# quadcopter-control-board.net
KiCad netlist of a schematic drawn in EAGLE
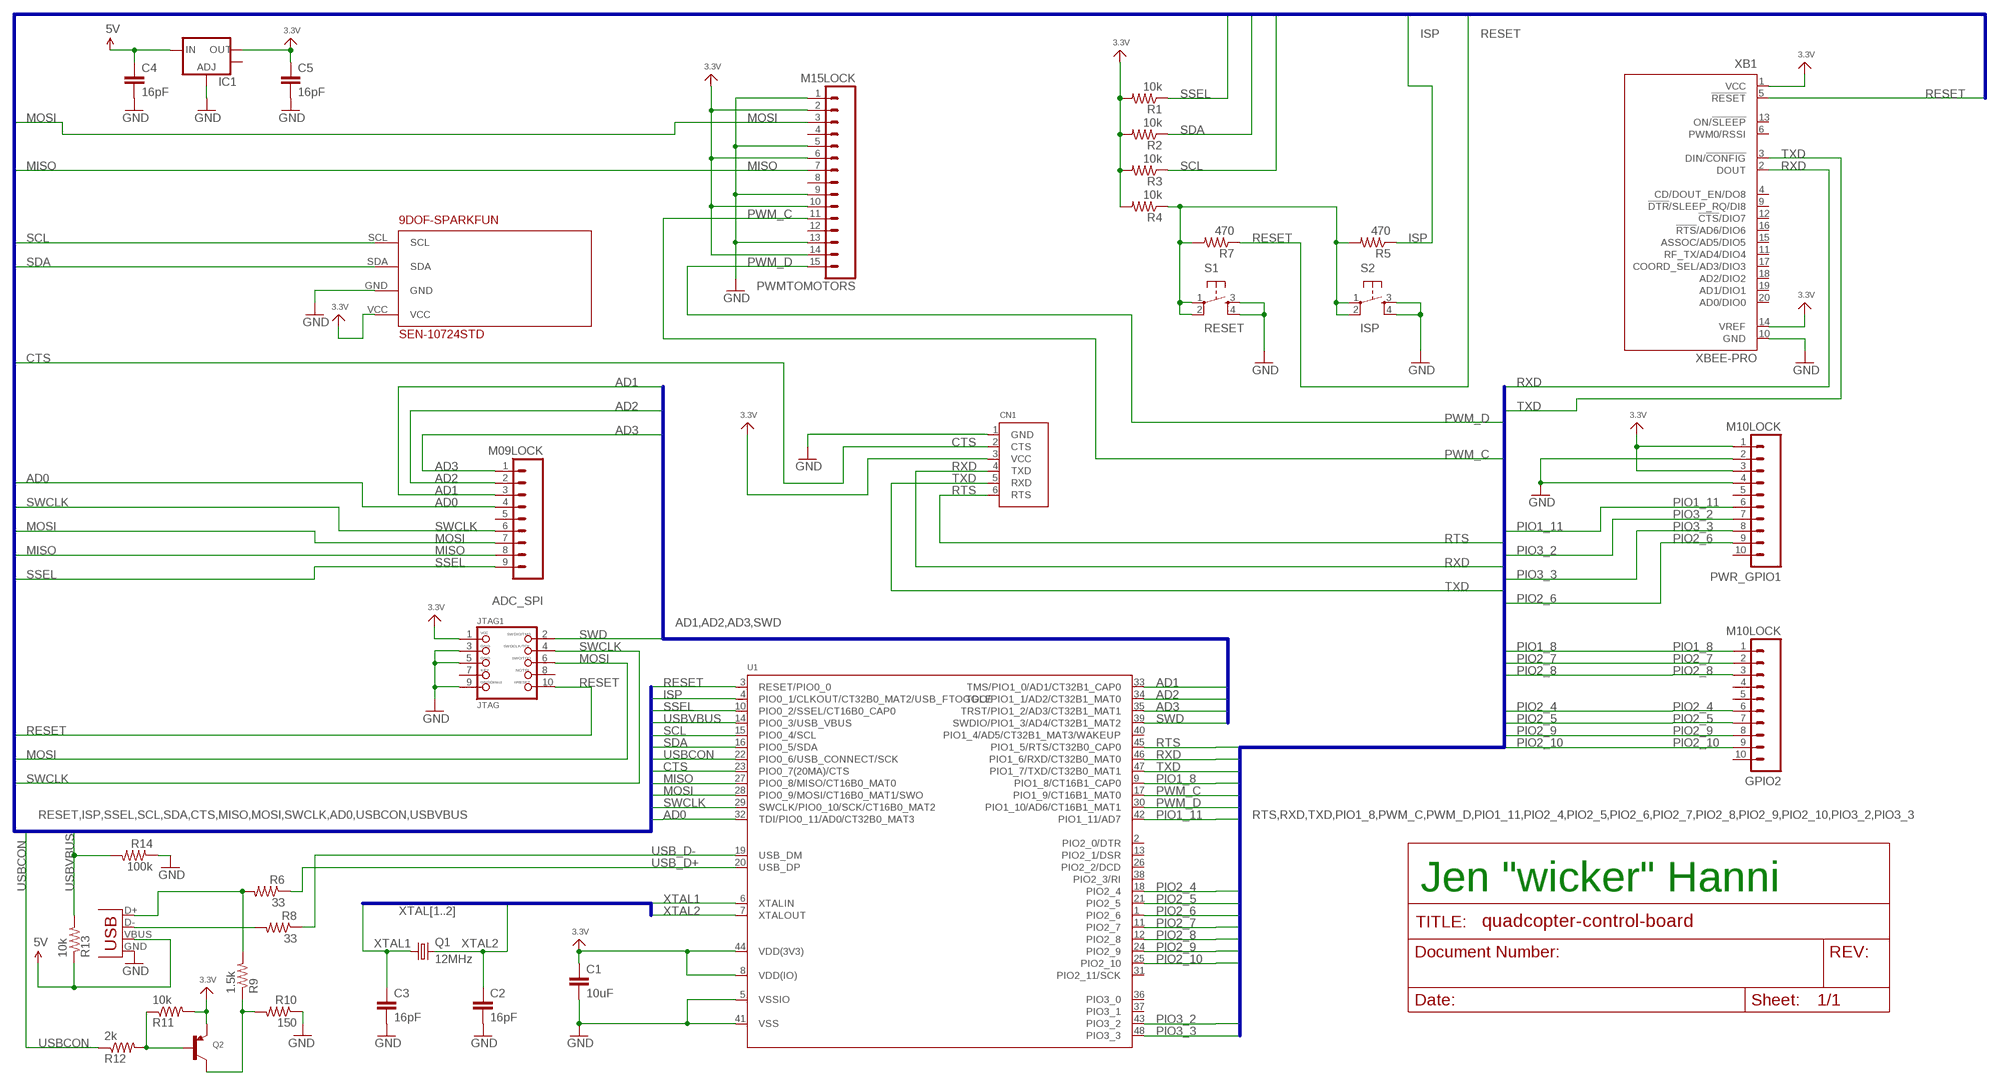
[diagram p0: schematic, sheet 1]

(export (version "E")
  (design (tool "Eeschema 10.0.6"))
  (components
    (comp (ref "9DOF-SPARKFUN")
      (value "SEN-10724STD")
      (footprint "eagle-import:SPARKFUN-9DOF")
      (libsource (lib "eagle-import") (part "SEN-10724STD"))
    )
    (comp (ref "ADC_SPI")
      (value "M09LOCK")
      (footprint "eagle-import:1X09_LOCK")
      (libsource (lib "eagle-import") (part "M09LOCK"))
    )
    (comp (ref "C1")
      (value "10uF")
      (footprint "eagle-import:0603-CAP")
      (libsource (lib "eagle-import") (part "CAP0603-CAP"))
    )
    (comp (ref "C2")
      (value "16pF")
      (footprint "eagle-import:0603-CAP")
      (libsource (lib "eagle-import") (part "CAP0603-CAP"))
    )
    (comp (ref "C3")
      (value "16pF")
      (footprint "eagle-import:0603-CAP")
      (libsource (lib "eagle-import") (part "CAP0603-CAP"))
    )
    (comp (ref "C4")
      (value "16pF")
      (footprint "eagle-import:0603-CAP")
      (libsource (lib "eagle-import") (part "CAP0603-CAP"))
    )
    (comp (ref "C5")
      (value "16pF")
      (footprint "eagle-import:0603-CAP")
      (libsource (lib "eagle-import") (part "CAP0603-CAP"))
    )
    (comp (ref "CN1")
      (value "FTDIUSBCABLE")
      (footprint "eagle-import:1X06_ROUND")
      (libsource (lib "eagle-import") (part "FTDIUSBCABLE"))
    )
    (comp (ref "GPIO2")
      (value "M10LOCK")
      (footprint "eagle-import:1X10_LOCK")
      (libsource (lib "eagle-import") (part "M10LOCK"))
    )
    (comp (ref "IC1")
      (value "V_REG_LM1117SOT223")
      (footprint "eagle-import:SOT223")
      (libsource (lib "eagle-import") (part "V_REG_LM1117SOT223"))
    )
    (comp (ref "JTAG1")
      (value "JTAG")
      (footprint "eagle-import:CORTEXM3_SWD10_MOLEX")
      (libsource (lib "eagle-import") (part "JTAG-CORTEXM3MOLEX"))
    )
    (comp (ref "PWMTOMOTORS")
      (value "M15LOCK")
      (footprint "eagle-import:1X15_LOCK")
      (libsource (lib "eagle-import") (part "M15LOCK"))
    )
    (comp (ref "PWR_GPIO1")
      (value "M10LOCK")
      (footprint "eagle-import:1X10_LOCK")
      (libsource (lib "eagle-import") (part "M10LOCK"))
    )
    (comp (ref "Q1")
      (value "12MHz")
      (footprint "eagle-import:CTS406")
      (libsource (lib "eagle-import") (part "CRYSTALCTS406"))
    )
    (comp (ref "Q2")
      (value "TRANSISTOR_PNPSOT23-REFLOW")
      (footprint "eagle-import:SOT23-R")
      (libsource (lib "eagle-import") (part "TRANSISTOR_PNPSOT23-REFLOW"))
    )
    (comp (ref "R1")
      (value "10k")
      (footprint "eagle-import:0603-RES")
      (libsource (lib "eagle-import") (part "RESISTOR0603-RES"))
    )
    (comp (ref "R2")
      (value "10k")
      (footprint "eagle-import:0603-RES")
      (libsource (lib "eagle-import") (part "RESISTOR0603-RES"))
    )
    (comp (ref "R3")
      (value "10k")
      (footprint "eagle-import:0603-RES")
      (libsource (lib "eagle-import") (part "RESISTOR0603-RES"))
    )
    (comp (ref "R4")
      (value "10k")
      (footprint "eagle-import:0603-RES")
      (libsource (lib "eagle-import") (part "RESISTOR0603-RES"))
    )
    (comp (ref "R5")
      (value "470")
      (footprint "eagle-import:0603-RES")
      (libsource (lib "eagle-import") (part "RESISTOR0603-RES"))
    )
    (comp (ref "R6")
      (value "33")
      (footprint "eagle-import:0603-RES")
      (libsource (lib "eagle-import") (part "RESISTOR0603-RES"))
    )
    (comp (ref "R7")
      (value "470")
      (footprint "eagle-import:0603-RES")
      (libsource (lib "eagle-import") (part "RESISTOR0603-RES"))
    )
    (comp (ref "R8")
      (value "33")
      (footprint "eagle-import:0603-RES")
      (libsource (lib "eagle-import") (part "RESISTOR0603-RES"))
    )
    (comp (ref "R9")
      (value "1.5k")
      (footprint "eagle-import:0603-RES")
      (libsource (lib "eagle-import") (part "RESISTOR0603-RES"))
    )
    (comp (ref "R10")
      (value "150")
      (footprint "eagle-import:0603-RES")
      (libsource (lib "eagle-import") (part "RESISTOR0603-RES"))
    )
    (comp (ref "R11")
      (value "10k")
      (footprint "eagle-import:0603-RES")
      (libsource (lib "eagle-import") (part "RESISTOR0603-RES"))
    )
    (comp (ref "R12")
      (value "2k")
      (footprint "eagle-import:0603-RES")
      (libsource (lib "eagle-import") (part "RESISTOR0603-RES"))
    )
    (comp (ref "R13")
      (value "10k")
      (footprint "eagle-import:0603-RES")
      (libsource (lib "eagle-import") (part "RESISTOR0603-RES"))
    )
    (comp (ref "R14")
      (value "100k")
      (footprint "eagle-import:0603-RES")
      (libsource (lib "eagle-import") (part "RESISTOR0603-RES"))
    )
    (comp (ref "S1")
      (value "RESET")
      (footprint "eagle-import:TACTILE_SWITCH_SMD")
      (libsource (lib "eagle-import") (part "TAC_SWITCHSMD"))
    )
    (comp (ref "S2")
      (value "ISP")
      (footprint "eagle-import:TACTILE_SWITCH_SMD")
      (libsource (lib "eagle-import") (part "TAC_SWITCHSMD"))
    )
    (comp (ref "U1")
      (value "LPC1343_QFP")
      (footprint "eagle-import:LQFP48")
      (fields (field (name "MANF") "NXP"))
      (libsource (lib "eagle-import") (part "LPC1343_QFP"))
    )
    (comp (ref "X1")
      (value "USB-SMD-NS")
      (footprint "eagle-import:USB-MINIB-NOSTOP")
      (libsource (lib "eagle-import") (part "USB-SMD-NS"))
    )
    (comp (ref "XB1")
      (value "XBEE-PRO")
      (footprint "eagle-import:XBEE-PRO")
      (libsource (lib "eagle-import") (part "XBEE-PRO"))
    )
  )
  (nets
    (net (code "1") (name "/AD0") (class "Default")
      (node (ref "ADC_SPI") (pin "4") (pinfunction "4_4") (pintype "passive"))
      (node (ref "U1") (pin "32") (pinfunction "TDI/PIO0_11/AD0/CT32B0_MAT3_32") (pintype "bidirectional"))
    )
    (net (code "2") (name "/AD1") (class "Default")
      (node (ref "ADC_SPI") (pin "3") (pinfunction "3_3") (pintype "passive"))
      (node (ref "U1") (pin "33") (pinfunction "TMS/PIO1_0/AD1/CT32B1_CAP0_33") (pintype "bidirectional"))
    )
    (net (code "3") (name "/AD2") (class "Default")
      (node (ref "ADC_SPI") (pin "2") (pinfunction "2_2") (pintype "passive"))
      (node (ref "U1") (pin "34") (pinfunction "TDO/PIO1_1/AD2/CT32B1_MAT0_34") (pintype "bidirectional"))
    )
    (net (code "4") (name "/AD3") (class "Default")
      (node (ref "ADC_SPI") (pin "1") (pinfunction "1_1") (pintype "passive"))
      (node (ref "U1") (pin "35") (pinfunction "TRST/PIO1_2/AD3/CT32B1_MAT1_35") (pintype "bidirectional"))
    )
    (net (code "5") (name "/CTS") (class "Default")
      (node (ref "CN1") (pin "2") (pinfunction "CTS_2") (pintype "bidirectional"))
      (node (ref "U1") (pin "23") (pinfunction "PIO0_7(20MA)/CTS_23") (pintype "bidirectional"))
    )
    (net (code "6") (name "/ISP") (class "Default")
      (node (ref "R5") (pin "1") (pinfunction "1_1") (pintype "passive"))
      (node (ref "U1") (pin "4") (pinfunction "PIO0_1/CLKOUT/CT32B0_MAT2/USB_FTOGGLE_4") (pintype "bidirectional"))
    )
    (net (code "7") (name "/MISO") (class "Default")
      (node (ref "ADC_SPI") (pin "8") (pinfunction "8_8") (pintype "passive"))
      (node (ref "PWMTOMOTORS") (pin "7") (pinfunction "7_7") (pintype "passive"))
      (node (ref "U1") (pin "27") (pinfunction "PIO0_8/MISO/CT16B0_MAT0_27") (pintype "bidirectional"))
    )
    (net (code "8") (name "/MOSI") (class "Default")
      (node (ref "ADC_SPI") (pin "7") (pinfunction "7_7") (pintype "passive"))
      (node (ref "JTAG1") (pin "6") (pinfunction "6_6") (pintype "passive"))
      (node (ref "PWMTOMOTORS") (pin "3") (pinfunction "3_3") (pintype "passive"))
      (node (ref "U1") (pin "28") (pinfunction "PIO0_9/MOSI/CT16B0_MAT1/SWO_28") (pintype "bidirectional"))
    )
    (net (code "9") (name "/PIO1_8") (class "Default")
      (node (ref "GPIO2") (pin "1") (pinfunction "1_1") (pintype "passive"))
      (node (ref "U1") (pin "9") (pinfunction "PIO1_8/CT16B1_CAP0_9") (pintype "bidirectional"))
    )
    (net (code "10") (name "/PIO1_11") (class "Default")
      (node (ref "PWR_GPIO1") (pin "6") (pinfunction "6_6") (pintype "passive"))
      (node (ref "U1") (pin "42") (pinfunction "PIO1_11/AD7_42") (pintype "bidirectional"))
    )
    (net (code "11") (name "/PIO2_4") (class "Default")
      (node (ref "GPIO2") (pin "6") (pinfunction "6_6") (pintype "passive"))
      (node (ref "U1") (pin "18") (pinfunction "PIO2_4_18") (pintype "bidirectional"))
    )
    (net (code "12") (name "/PIO2_5") (class "Default")
      (node (ref "GPIO2") (pin "7") (pinfunction "7_7") (pintype "passive"))
      (node (ref "U1") (pin "21") (pinfunction "PIO2_5_21") (pintype "bidirectional"))
    )
    (net (code "13") (name "/PIO2_6") (class "Default")
      (node (ref "PWR_GPIO1") (pin "9") (pinfunction "9_9") (pintype "passive"))
      (node (ref "U1") (pin "1") (pinfunction "PIO2_6_1") (pintype "bidirectional"))
    )
    (net (code "14") (name "/PIO2_7") (class "Default")
      (node (ref "GPIO2") (pin "2") (pinfunction "2_2") (pintype "passive"))
      (node (ref "U1") (pin "11") (pinfunction "PIO2_7_11") (pintype "bidirectional"))
    )
    (net (code "15") (name "/PIO2_8") (class "Default")
      (node (ref "GPIO2") (pin "3") (pinfunction "3_3") (pintype "passive"))
      (node (ref "U1") (pin "12") (pinfunction "PIO2_8_12") (pintype "bidirectional"))
    )
    (net (code "16") (name "/PIO2_9") (class "Default")
      (node (ref "GPIO2") (pin "8") (pinfunction "8_8") (pintype "passive"))
      (node (ref "U1") (pin "24") (pinfunction "PIO2_9_24") (pintype "bidirectional"))
    )
    (net (code "17") (name "/PIO2_10") (class "Default")
      (node (ref "GPIO2") (pin "9") (pinfunction "9_9") (pintype "passive"))
      (node (ref "U1") (pin "25") (pinfunction "PIO2_10_25") (pintype "bidirectional"))
    )
    (net (code "18") (name "/PIO3_2") (class "Default")
      (node (ref "PWR_GPIO1") (pin "7") (pinfunction "7_7") (pintype "passive"))
      (node (ref "U1") (pin "43") (pinfunction "PIO3_2_43") (pintype "bidirectional"))
    )
    (net (code "19") (name "/PIO3_3") (class "Default")
      (node (ref "PWR_GPIO1") (pin "8") (pinfunction "8_8") (pintype "passive"))
      (node (ref "U1") (pin "48") (pinfunction "PIO3_3_48") (pintype "bidirectional"))
    )
    (net (code "20") (name "/PWM_C") (class "Default")
      (node (ref "PWMTOMOTORS") (pin "11") (pinfunction "11_11") (pintype "passive"))
      (node (ref "U1") (pin "17") (pinfunction "PIO1_9/CT16B1_MAT0_17") (pintype "bidirectional"))
    )
    (net (code "21") (name "/PWM_D") (class "Default")
      (node (ref "PWMTOMOTORS") (pin "15") (pinfunction "15_15") (pintype "passive"))
      (node (ref "U1") (pin "30") (pinfunction "PIO1_10/AD6/CT16B1_MAT1_30") (pintype "bidirectional"))
    )
    (net (code "22") (name "/RESET") (class "Default")
      (node (ref "JTAG1") (pin "10") (pinfunction "10_10") (pintype "passive"))
      (node (ref "R7") (pin "1") (pinfunction "1_1") (pintype "passive"))
      (node (ref "U1") (pin "3") (pinfunction "RESET/PIO0_0_3") (pintype "bidirectional"))
      (node (ref "XB1") (pin "5") (pinfunction "~{RESET}_5") (pintype "input"))
    )
    (net (code "23") (name "/RTS") (class "Default")
      (node (ref "CN1") (pin "6") (pinfunction "RTS_6") (pintype "bidirectional"))
      (node (ref "U1") (pin "45") (pinfunction "PIO1_5/RTS/CT32B0_CAP0_45") (pintype "bidirectional"))
    )
    (net (code "24") (name "/RXD") (class "Default")
      (node (ref "CN1") (pin "4") (pinfunction "TXD_4") (pintype "bidirectional"))
      (node (ref "U1") (pin "46") (pinfunction "PIO1_6/RXD/CT32B0_MAT0_46") (pintype "bidirectional"))
      (node (ref "XB1") (pin "2") (pinfunction "DOUT_2") (pintype "output"))
    )
    (net (code "25") (name "/SCL") (class "Default")
      (node (ref "9DOF-SPARKFUN") (pin "SCL") (pinfunction "SCL_SCL") (pintype "bidirectional"))
      (node (ref "R3") (pin "1") (pinfunction "1_1") (pintype "passive"))
      (node (ref "U1") (pin "15") (pinfunction "PIO0_4/SCL_15") (pintype "bidirectional"))
    )
    (net (code "26") (name "/SDA") (class "Default")
      (node (ref "9DOF-SPARKFUN") (pin "SDA") (pinfunction "SDA_SDA") (pintype "bidirectional"))
      (node (ref "R2") (pin "1") (pinfunction "1_1") (pintype "passive"))
      (node (ref "U1") (pin "16") (pinfunction "PIO0_5/SDA_16") (pintype "bidirectional"))
    )
    (net (code "27") (name "/SSEL") (class "Default")
      (node (ref "ADC_SPI") (pin "9") (pinfunction "9_9") (pintype "passive"))
      (node (ref "R1") (pin "1") (pinfunction "1_1") (pintype "passive"))
      (node (ref "U1") (pin "10") (pinfunction "PIO0_2/SSEL/CT16B0_CAP0_10") (pintype "bidirectional"))
    )
    (net (code "28") (name "/SWCLK") (class "Default")
      (node (ref "ADC_SPI") (pin "6") (pinfunction "6_6") (pintype "passive"))
      (node (ref "JTAG1") (pin "4") (pinfunction "4_4") (pintype "passive"))
      (node (ref "U1") (pin "29") (pinfunction "SWCLK/PIO0_10/SCK/CT16B0_MAT2_29") (pintype "bidirectional"))
    )
    (net (code "29") (name "/SWD") (class "Default")
      (node (ref "JTAG1") (pin "2") (pinfunction "2_2") (pintype "passive"))
      (node (ref "U1") (pin "39") (pinfunction "SWDIO/PIO1_3/AD4/CT32B1_MAT2_39") (pintype "bidirectional"))
    )
    (net (code "30") (name "/TXD") (class "Default")
      (node (ref "CN1") (pin "5") (pinfunction "RXD_5") (pintype "bidirectional"))
      (node (ref "U1") (pin "47") (pinfunction "PIO1_7/TXD/CT32B0_MAT1_47") (pintype "bidirectional"))
      (node (ref "XB1") (pin "3") (pinfunction "DIN/~{CONFIG}_3") (pintype "input"))
    )
    (net (code "31") (name "/USBCON") (class "Default")
      (node (ref "R12") (pin "1") (pinfunction "1_1") (pintype "passive"))
      (node (ref "U1") (pin "22") (pinfunction "PIO0_6/USB_CONNECT/SCK_22") (pintype "bidirectional"))
    )
    (net (code "32") (name "/USBVBUS") (class "Default")
      (node (ref "R13") (pin "2") (pinfunction "2_2") (pintype "passive"))
      (node (ref "R14") (pin "2") (pinfunction "2_2") (pintype "passive"))
      (node (ref "U1") (pin "14") (pinfunction "PIO0_3/USB_VBUS_14") (pintype "bidirectional"))
    )
    (net (code "33") (name "/USB_D+") (class "Default")
      (node (ref "R6") (pin "1") (pinfunction "1_1") (pintype "passive"))
      (node (ref "U1") (pin "20") (pinfunction "USB_DP_20") (pintype "bidirectional"))
    )
    (net (code "34") (name "/USB_D-") (class "Default")
      (node (ref "R8") (pin "1") (pinfunction "1_1") (pintype "passive"))
      (node (ref "U1") (pin "19") (pinfunction "USB_DM_19") (pintype "bidirectional"))
    )
    (net (code "35") (name "/XTAL1") (class "Default")
      (node (ref "C3") (pin "1") (pinfunction "1_1") (pintype "passive"))
      (node (ref "Q1") (pin "1") (pinfunction "1_1") (pintype "passive"))
      (node (ref "U1") (pin "6") (pinfunction "XTALIN_6") (pintype "input"))
    )
    (net (code "36") (name "/XTAL2") (class "Default")
      (node (ref "C2") (pin "1") (pinfunction "1_1") (pintype "passive"))
      (node (ref "Q1") (pin "3") (pinfunction "2_3") (pintype "passive"))
      (node (ref "U1") (pin "7") (pinfunction "XTALOUT_7") (pintype "output"))
    )
    (net (code "41") (name "3.3V") (class "Default")
      (node (ref "9DOF-SPARKFUN") (pin "VCC") (pinfunction "VCC_VCC") (pintype "power_in"))
      (node (ref "C1") (pin "1") (pinfunction "1_1") (pintype "passive"))
      (node (ref "C5") (pin "1") (pinfunction "1_1") (pintype "passive"))
      (node (ref "CN1") (pin "3") (pinfunction "VCC_3") (pintype "bidirectional"))
      (node (ref "IC1") (pin "2") (pinfunction "OUT_2") (pintype "output"))
      (node (ref "JTAG1") (pin "1") (pinfunction "1_1") (pintype "passive"))
      (node (ref "PWMTOMOTORS") (pin "10") (pinfunction "10_10") (pintype "passive"))
      (node (ref "PWMTOMOTORS") (pin "14") (pinfunction "14_14") (pintype "passive"))
      (node (ref "PWMTOMOTORS") (pin "2") (pinfunction "2_2") (pintype "passive"))
      (node (ref "PWMTOMOTORS") (pin "6") (pinfunction "6_6") (pintype "passive"))
      (node (ref "PWR_GPIO1") (pin "1") (pinfunction "1_1") (pintype "passive"))
      (node (ref "PWR_GPIO1") (pin "3") (pinfunction "3_3") (pintype "passive"))
      (node (ref "Q2") (pin "2") (pinfunction "E_2") (pintype "passive"))
      (node (ref "R1") (pin "2") (pinfunction "2_2") (pintype "passive"))
      (node (ref "R11") (pin "2") (pinfunction "2_2") (pintype "passive"))
      (node (ref "R2") (pin "2") (pinfunction "2_2") (pintype "passive"))
      (node (ref "R3") (pin "2") (pinfunction "2_2") (pintype "passive"))
      (node (ref "R4") (pin "2") (pinfunction "2_2") (pintype "passive"))
      (node (ref "U1") (pin "44") (pinfunction "VDD(3V3)_44") (pintype "power_in"))
      (node (ref "U1") (pin "8") (pinfunction "VDD(IO)_8") (pintype "power_in"))
      (node (ref "XB1") (pin "1") (pinfunction "VCC_1") (pintype "power_in"))
      (node (ref "XB1") (pin "14") (pinfunction "VREF_14") (pintype "input"))
    )
    (net (code "42") (name "5V") (class "Default")
      (node (ref "C4") (pin "1") (pinfunction "1_1") (pintype "passive"))
      (node (ref "IC1") (pin "3") (pinfunction "IN_3") (pintype "input"))
      (node (ref "R13") (pin "1") (pinfunction "1_1") (pintype "passive"))
      (node (ref "X1") (pin "VBUS") (pinfunction "VBUS_VBUS") (pintype "bidirectional"))
    )
    (net (code "43") (name "GND") (class "Default")
      (node (ref "9DOF-SPARKFUN") (pin "GND") (pinfunction "GND_GND") (pintype "power_in"))
      (node (ref "C1") (pin "2") (pinfunction "2_2") (pintype "passive"))
      (node (ref "C2") (pin "2") (pinfunction "2_2") (pintype "passive"))
      (node (ref "C3") (pin "2") (pinfunction "2_2") (pintype "passive"))
      (node (ref "C4") (pin "2") (pinfunction "2_2") (pintype "passive"))
      (node (ref "C5") (pin "2") (pinfunction "2_2") (pintype "passive"))
      (node (ref "CN1") (pin "1") (pinfunction "GND_1") (pintype "bidirectional"))
      (node (ref "IC1") (pin "1") (pinfunction "ADJ_1") (pintype "input"))
      (node (ref "JTAG1") (pin "3") (pinfunction "3_3") (pintype "passive"))
      (node (ref "JTAG1") (pin "5") (pinfunction "5_5") (pintype "passive"))
      (node (ref "JTAG1") (pin "9") (pinfunction "9_9") (pintype "passive"))
      (node (ref "PWMTOMOTORS") (pin "1") (pinfunction "1_1") (pintype "passive"))
      (node (ref "PWMTOMOTORS") (pin "13") (pinfunction "13_13") (pintype "passive"))
      (node (ref "PWMTOMOTORS") (pin "5") (pinfunction "5_5") (pintype "passive"))
      (node (ref "PWMTOMOTORS") (pin "9") (pinfunction "9_9") (pintype "passive"))
      (node (ref "PWR_GPIO1") (pin "2") (pinfunction "2_2") (pintype "passive"))
      (node (ref "PWR_GPIO1") (pin "4") (pinfunction "4_4") (pintype "passive"))
      (node (ref "R10") (pin "1") (pinfunction "1_1") (pintype "passive"))
      (node (ref "R14") (pin "1") (pinfunction "1_1") (pintype "passive"))
      (node (ref "S1") (pin "3") (pinfunction "3_3") (pintype "passive"))
      (node (ref "S1") (pin "4") (pinfunction "4_4") (pintype "passive"))
      (node (ref "S2") (pin "3") (pinfunction "3_3") (pintype "passive"))
      (node (ref "S2") (pin "4") (pinfunction "4_4") (pintype "passive"))
      (node (ref "U1") (pin "41") (pinfunction "VSS_41") (pintype "power_in"))
      (node (ref "U1") (pin "5") (pinfunction "VSSIO_5") (pintype "power_in"))
      (node (ref "X1") (pin "GND") (pinfunction "GND_GND") (pintype "bidirectional"))
      (node (ref "XB1") (pin "10") (pinfunction "GND_10") (pintype "power_in"))
    )
    (net (code "44") (name "Net-(Q2-B)") (class "Default")
      (node (ref "Q2") (pin "1") (pinfunction "B_1") (pintype "passive"))
      (node (ref "R11") (pin "1") (pinfunction "1_1") (pintype "passive"))
      (node (ref "R12") (pin "2") (pinfunction "2_2") (pintype "passive"))
    )
    (net (code "45") (name "Net-(Q2-C)") (class "Default")
      (node (ref "Q2") (pin "3") (pinfunction "C_3") (pintype "passive"))
      (node (ref "R10") (pin "2") (pinfunction "2_2") (pintype "passive"))
      (node (ref "R9") (pin "1") (pinfunction "1_1") (pintype "passive"))
    )
    (net (code "46") (name "Net-(R4-Pad1)") (class "Default")
      (node (ref "R4") (pin "1") (pinfunction "1_1") (pintype "passive"))
      (node (ref "R5") (pin "2") (pinfunction "2_2") (pintype "passive"))
      (node (ref "R7") (pin "2") (pinfunction "2_2") (pintype "passive"))
      (node (ref "S1") (pin "1") (pinfunction "1_1") (pintype "passive"))
      (node (ref "S1") (pin "2") (pinfunction "2_2") (pintype "passive"))
      (node (ref "S2") (pin "1") (pinfunction "1_1") (pintype "passive"))
      (node (ref "S2") (pin "2") (pinfunction "2_2") (pintype "passive"))
    )
    (net (code "47") (name "Net-(R6-Pad2)") (class "Default")
      (node (ref "R6") (pin "2") (pinfunction "2_2") (pintype "passive"))
      (node (ref "R9") (pin "2") (pinfunction "2_2") (pintype "passive"))
      (node (ref "X1") (pin "D+") (pinfunction "D+_D+") (pintype "bidirectional"))
    )
    (net (code "48") (name "Net-(R8-Pad2)") (class "Default")
      (node (ref "R8") (pin "2") (pinfunction "2_2") (pintype "passive"))
      (node (ref "X1") (pin "D-") (pinfunction "D-_D-") (pintype "bidirectional"))
    )
    (net (code "49") (name "unconnected-(ADC_SPI-Pad5)") (class "Default")
      (node (ref "ADC_SPI") (pin "5") (pinfunction "5_5") (pintype "passive"))
    )
    (net (code "50") (name "unconnected-(GPIO2-Pad4)") (class "Default")
      (node (ref "GPIO2") (pin "4") (pinfunction "4_4") (pintype "passive"))
    )
    (net (code "51") (name "unconnected-(GPIO2-Pad5)") (class "Default")
      (node (ref "GPIO2") (pin "5") (pinfunction "5_5") (pintype "passive"))
    )
    (net (code "52") (name "unconnected-(GPIO2-Pad10)") (class "Default")
      (node (ref "GPIO2") (pin "10") (pinfunction "10_10") (pintype "passive"))
    )
    (net (code "53") (name "unconnected-(IC1-OUT-Pad4)") (class "Default")
      (node (ref "IC1") (pin "4") (pinfunction "OUT_4") (pintype "output"))
    )
    (net (code "54") (name "unconnected-(JTAG1-Pad7)") (class "Default")
      (node (ref "JTAG1") (pin "7") (pinfunction "7_7") (pintype "passive"))
    )
    (net (code "55") (name "unconnected-(JTAG1-Pad8)") (class "Default")
      (node (ref "JTAG1") (pin "8") (pinfunction "8_8") (pintype "passive"))
    )
    (net (code "56") (name "unconnected-(PWMTOMOTORS-Pad4)") (class "Default")
      (node (ref "PWMTOMOTORS") (pin "4") (pinfunction "4_4") (pintype "passive"))
    )
    (net (code "57") (name "unconnected-(PWMTOMOTORS-Pad8)") (class "Default")
      (node (ref "PWMTOMOTORS") (pin "8") (pinfunction "8_8") (pintype "passive"))
    )
    (net (code "58") (name "unconnected-(PWMTOMOTORS-Pad12)") (class "Default")
      (node (ref "PWMTOMOTORS") (pin "12") (pinfunction "12_12") (pintype "passive"))
    )
    (net (code "59") (name "unconnected-(PWR_GPIO1-Pad5)") (class "Default")
      (node (ref "PWR_GPIO1") (pin "5") (pinfunction "5_5") (pintype "passive"))
    )
    (net (code "60") (name "unconnected-(PWR_GPIO1-Pad10)") (class "Default")
      (node (ref "PWR_GPIO1") (pin "10") (pinfunction "10_10") (pintype "passive"))
    )
    (net (code "61") (name "unconnected-(U1-PIO1_4{slash}AD5{slash}CT32B1_MAT3{slash}WAKEUP-Pad40)") (class "Default")
      (node (ref "U1") (pin "40") (pinfunction "PIO1_4/AD5/CT32B1_MAT3/WAKEUP_40") (pintype "bidirectional"))
    )
    (net (code "62") (name "unconnected-(U1-PIO2_0{slash}DTR-Pad2)") (class "Default")
      (node (ref "U1") (pin "2") (pinfunction "PIO2_0/DTR_2") (pintype "bidirectional"))
    )
    (net (code "63") (name "unconnected-(U1-PIO2_1{slash}DSR-Pad13)") (class "Default")
      (node (ref "U1") (pin "13") (pinfunction "PIO2_1/DSR_13") (pintype "bidirectional"))
    )
    (net (code "64") (name "unconnected-(U1-PIO2_2{slash}DCD-Pad26)") (class "Default")
      (node (ref "U1") (pin "26") (pinfunction "PIO2_2/DCD_26") (pintype "bidirectional"))
    )
    (net (code "65") (name "unconnected-(U1-PIO2_3{slash}RI-Pad38)") (class "Default")
      (node (ref "U1") (pin "38") (pinfunction "PIO2_3/RI_38") (pintype "bidirectional"))
    )
    (net (code "66") (name "unconnected-(U1-PIO2_11{slash}SCK-Pad31)") (class "Default")
      (node (ref "U1") (pin "31") (pinfunction "PIO2_11/SCK_31") (pintype "bidirectional"))
    )
    (net (code "67") (name "unconnected-(U1-PIO3_0-Pad36)") (class "Default")
      (node (ref "U1") (pin "36") (pinfunction "PIO3_0_36") (pintype "bidirectional"))
    )
    (net (code "68") (name "unconnected-(U1-PIO3_1-Pad37)") (class "Default")
      (node (ref "U1") (pin "37") (pinfunction "PIO3_1_37") (pintype "bidirectional"))
    )
    (net (code "69") (name "unconnected-(XB1-AD0{slash}DIO0-Pad20)") (class "Default")
      (node (ref "XB1") (pin "20") (pinfunction "AD0/DIO0_20") (pintype "bidirectional"))
    )
    (net (code "70") (name "unconnected-(XB1-AD1{slash}DIO1-Pad19)") (class "Default")
      (node (ref "XB1") (pin "19") (pinfunction "AD1/DIO1_19") (pintype "bidirectional"))
    )
    (net (code "71") (name "unconnected-(XB1-AD2{slash}DIO2-Pad18)") (class "Default")
      (node (ref "XB1") (pin "18") (pinfunction "AD2/DIO2_18") (pintype "bidirectional"))
    )
    (net (code "72") (name "unconnected-(XB1-ASSOC{slash}AD5{slash}DIO5-Pad15)") (class "Default")
      (node (ref "XB1") (pin "15") (pinfunction "ASSOC/AD5/DIO5_15") (pintype "bidirectional"))
    )
    (net (code "73") (name "unconnected-(XB1-CD{slash}DOUT_EN{slash}DO8-Pad4)") (class "Default")
      (node (ref "XB1") (pin "4") (pinfunction "CD/DOUT_EN/DO8_4") (pintype "output"))
    )
    (net (code "74") (name "unconnected-(XB1-COORD_SEL{slash}AD3{slash}DIO3-Pad17)") (class "Default")
      (node (ref "XB1") (pin "17") (pinfunction "COORD_SEL/AD3/DIO3_17") (pintype "bidirectional"))
    )
    (net (code "75") (name "unconnected-(XB1-ON{slash}~{SLEEP}-Pad13)") (class "Default")
      (node (ref "XB1") (pin "13") (pinfunction "ON/~{SLEEP}_13") (pintype "output"))
    )
    (net (code "76") (name "unconnected-(XB1-PWM0{slash}RSSI-Pad6)") (class "Default")
      (node (ref "XB1") (pin "6") (pinfunction "PWM0/RSSI_6") (pintype "output"))
    )
    (net (code "77") (name "unconnected-(XB1-RF_TX{slash}AD4{slash}DIO4-Pad11)") (class "Default")
      (node (ref "XB1") (pin "11") (pinfunction "RF_TX/AD4/DIO4_11") (pintype "bidirectional"))
    )
    (net (code "78") (name "unconnected-(XB1-~{CTS}{slash}DIO7-Pad12)") (class "Default")
      (node (ref "XB1") (pin "12") (pinfunction "~{CTS}/DIO7_12") (pintype "bidirectional"))
    )
    (net (code "79") (name "unconnected-(XB1-~{DTR}{slash}SLEEP_RQ{slash}DI8-Pad9)") (class "Default")
      (node (ref "XB1") (pin "9") (pinfunction "~{DTR}/SLEEP_RQ/DI8_9") (pintype "bidirectional"))
    )
    (net (code "80") (name "unconnected-(XB1-~{RTS}{slash}AD6{slash}DIO6-Pad16)") (class "Default")
      (node (ref "XB1") (pin "16") (pinfunction "~{RTS}/AD6/DIO6_16") (pintype "bidirectional"))
    )
  )
)
